# Beaglebone_black.net
KiCad netlist of a schematic drawn in Altium Designer
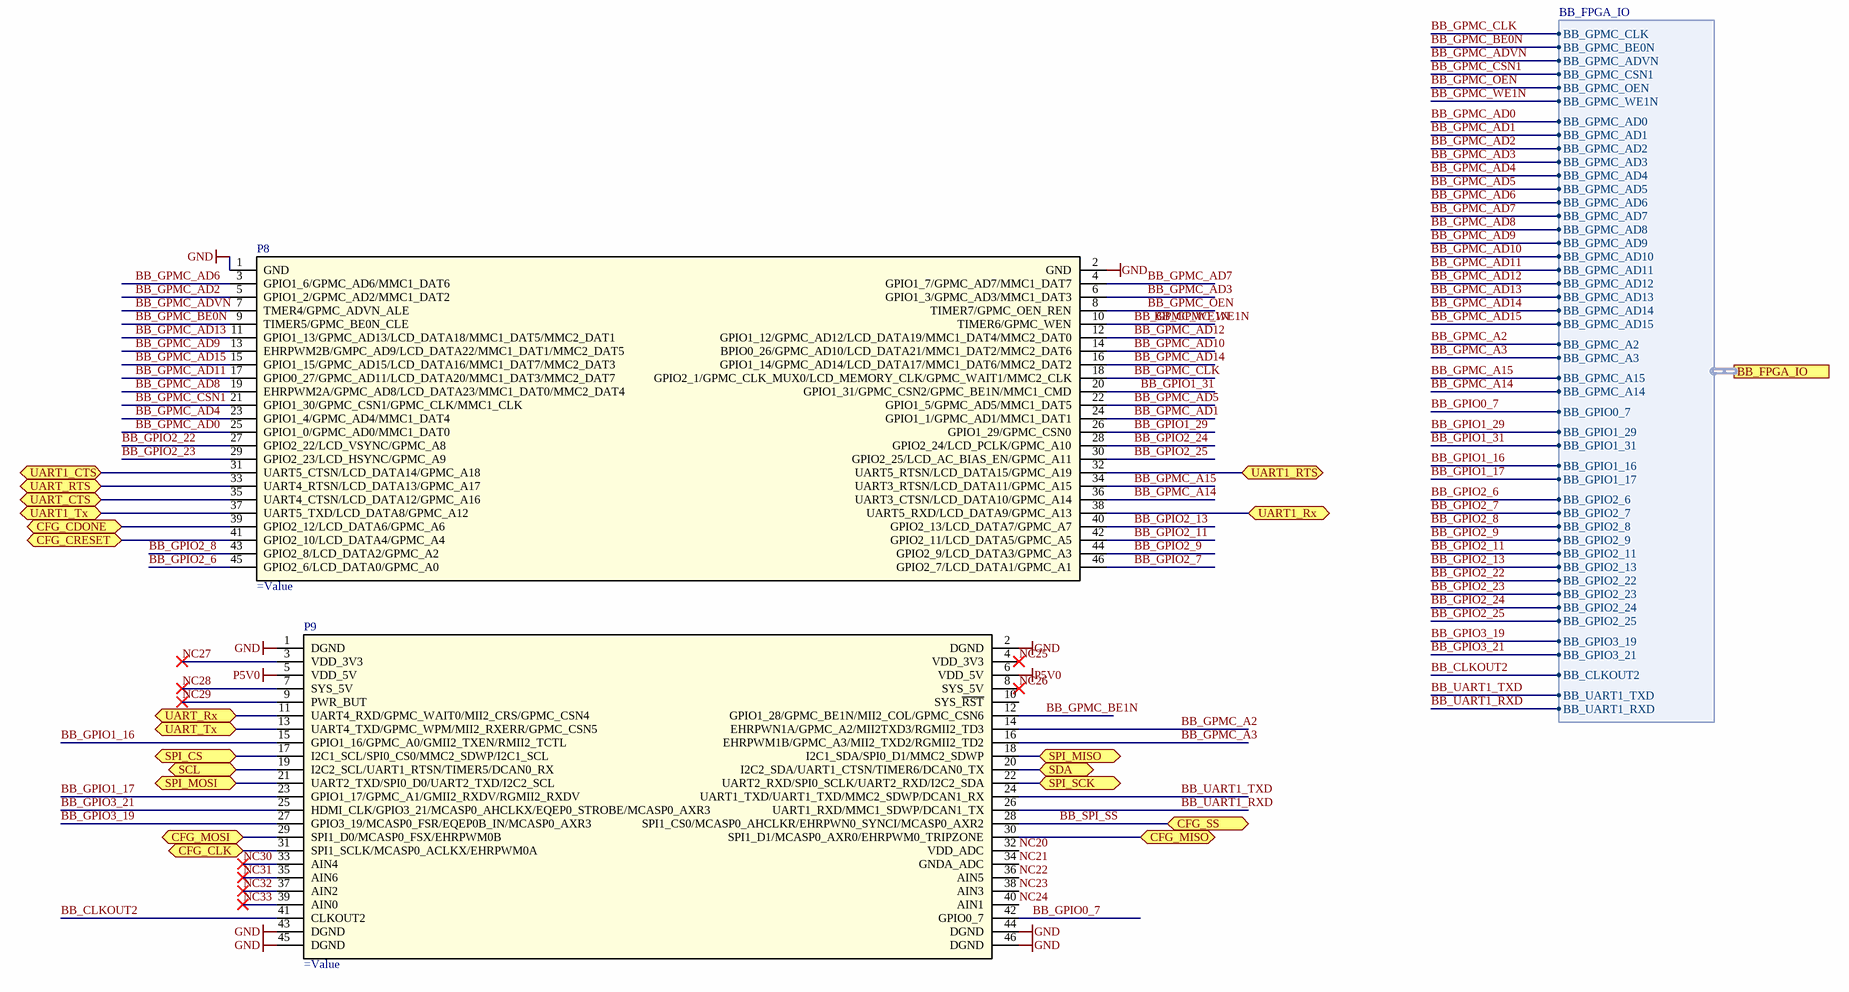
[diagram p0: Beaglebone_black.SchDoc]

(export (version "E")
  (design (tool "Eeschema 10.0.6"))
  (components
    (comp (ref "P8")
      (value "~")
      (footprint "MOD_BEAGLEBONE_P8")
      (description "Beagle_Bone_Black_P8")
      (fields (field (name "MANUFACTURER") "Samtec Inc"))
      (libsource (lib "LIBRARY_SCH") (part "MOD_Beagle_Bone_Black_P8-SSQ"))
    )
    (comp (ref "P9")
      (value "~")
      (footprint "MOD_BEAGLEBONE_P9")
      (description "Beagle_Bone_Black_P9")
      (fields (field (name "MANUFACTURER") "Samtec Inc"))
      (libsource (lib "LIBRARY_SCH") (part "MOD_Beagle_Bone_Black_P9-SSQ"))
    )
  )
  (nets
    (net (code "2") (name "/BB_CLKOUT2") (class "Default")
      (node (ref "P9") (pin "41") (pinfunction "CLKOUT2_41") (pintype "passive"))
    )
    (net (code "3") (name "/BB_GPIO0_7") (class "Default")
      (node (ref "P9") (pin "42") (pinfunction "GPIO0_7_42") (pintype "passive"))
    )
    (net (code "4") (name "/BB_GPIO1_16") (class "Default")
      (node (ref "P9") (pin "15") (pinfunction "GPIO1_16/GPMC_A0/GMII2_TXEN/RMII2_TCTL_15") (pintype "passive"))
    )
    (net (code "5") (name "/BB_GPIO1_17") (class "Default")
      (node (ref "P9") (pin "23") (pinfunction "GPIO1_17/GPMC_A1/GMII2_RXDV/RGMII2_RXDV_23") (pintype "passive"))
    )
    (net (code "6") (name "/BB_GPIO1_29") (class "Default")
      (node (ref "P8") (pin "26") (pinfunction "GPIO1_29/GPMC_CSN0_26") (pintype "passive"))
    )
    (net (code "7") (name "/BB_GPIO1_31") (class "Default")
      (node (ref "P8") (pin "20") (pinfunction "GPIO1_31/GPMC_CSN2/GPMC_BE1N/MMC1_CMD_20") (pintype "passive"))
    )
    (net (code "8") (name "/BB_GPIO2_6") (class "Default")
      (node (ref "P8") (pin "45") (pinfunction "GPIO2_6/LCD_DATA0/GPMC_A0_45") (pintype "passive"))
    )
    (net (code "9") (name "/BB_GPIO2_7") (class "Default")
      (node (ref "P8") (pin "46") (pinfunction "GPIO2_7/LCD_DATA1/GPMC_A1_46") (pintype "passive"))
    )
    (net (code "10") (name "/BB_GPIO2_8") (class "Default")
      (node (ref "P8") (pin "43") (pinfunction "GPIO2_8/LCD_DATA2/GPMC_A2_43") (pintype "passive"))
    )
    (net (code "11") (name "/BB_GPIO2_9") (class "Default")
      (node (ref "P8") (pin "44") (pinfunction "GPIO2_9/LCD_DATA3/GPMC_A3_44") (pintype "passive"))
    )
    (net (code "12") (name "/BB_GPIO2_11") (class "Default")
      (node (ref "P8") (pin "42") (pinfunction "GPIO2_11/LCD_DATA5/GPMC_A5_42") (pintype "passive"))
    )
    (net (code "13") (name "/BB_GPIO2_13") (class "Default")
      (node (ref "P8") (pin "40") (pinfunction "GPIO2_13/LCD_DATA7/GPMC_A7_40") (pintype "passive"))
    )
    (net (code "14") (name "/BB_GPIO2_22") (class "Default")
      (node (ref "P8") (pin "27") (pinfunction "GPIO2_22/LCD_VSYNC/GPMC_A8_27") (pintype "passive"))
    )
    (net (code "15") (name "/BB_GPIO2_23") (class "Default")
      (node (ref "P8") (pin "29") (pinfunction "GPIO2_23/LCD_HSYNC/GPMC_A9_29") (pintype "passive"))
    )
    (net (code "16") (name "/BB_GPIO2_24") (class "Default")
      (node (ref "P8") (pin "28") (pinfunction "GPIO2_24/LCD_PCLK/GPMC_A10_28") (pintype "passive"))
    )
    (net (code "17") (name "/BB_GPIO2_25") (class "Default")
      (node (ref "P8") (pin "30") (pinfunction "GPIO2_25/LCD_AC_BIAS_EN/GPMC_A11_30") (pintype "passive"))
    )
    (net (code "18") (name "/BB_GPIO3_19") (class "Default")
      (node (ref "P9") (pin "27") (pinfunction "GPIO3_19/MCASP0_FSR/EQEP0B_IN/MCASP0_AXR3_27") (pintype "passive"))
    )
    (net (code "19") (name "/BB_GPIO3_21") (class "Default")
      (node (ref "P9") (pin "25") (pinfunction "HDMI_CLK/GPIO3_21/MCASP0_AHCLKX/EQEP0_STROBE/MCASP0_AXR3_25") (pintype "passive"))
    )
    (net (code "20") (name "/BB_GPMC_A2") (class "Default")
      (node (ref "P9") (pin "14") (pinfunction "EHRPWN1A/GPMC_A2/MII2TXD3/RGMII2_TD3_14") (pintype "passive"))
    )
    (net (code "21") (name "/BB_GPMC_A3") (class "Default")
      (node (ref "P9") (pin "16") (pinfunction "EHRPWM1B/GPMC_A3/MII2_TXD2/RGMII2_TD2_16") (pintype "passive"))
    )
    (net (code "22") (name "/BB_GPMC_A14") (class "Default")
      (node (ref "P8") (pin "36") (pinfunction "UART3_CTSN/LCD_DATA10/GPMC_A14_36") (pintype "passive"))
    )
    (net (code "23") (name "/BB_GPMC_A15") (class "Default")
      (node (ref "P8") (pin "34") (pinfunction "UART3_RTSN/LCD_DATA11/GPMC_A15_34") (pintype "passive"))
    )
    (net (code "24") (name "/BB_GPMC_AD0") (class "Default")
      (node (ref "P8") (pin "25") (pinfunction "GPIO1_0/GPMC_AD0/MMC1_DAT0_25") (pintype "passive"))
    )
    (net (code "25") (name "/BB_GPMC_AD1") (class "Default")
      (node (ref "P8") (pin "24") (pinfunction "GPIO1_1/GPMC_AD1/MMC1_DAT1_24") (pintype "passive"))
    )
    (net (code "26") (name "/BB_GPMC_AD2") (class "Default")
      (node (ref "P8") (pin "5") (pinfunction "GPIO1_2/GPMC_AD2/MMC1_DAT2_5") (pintype "passive"))
    )
    (net (code "27") (name "/BB_GPMC_AD3") (class "Default")
      (node (ref "P8") (pin "6") (pinfunction "GPIO1_3/GPMC_AD3/MMC1_DAT3_6") (pintype "passive"))
    )
    (net (code "28") (name "/BB_GPMC_AD4") (class "Default")
      (node (ref "P8") (pin "23") (pinfunction "GPIO1_4/GPMC_AD4/MMC1_DAT4_23") (pintype "passive"))
    )
    (net (code "29") (name "/BB_GPMC_AD5") (class "Default")
      (node (ref "P8") (pin "22") (pinfunction "GPIO1_5/GPMC_AD5/MMC1_DAT5_22") (pintype "passive"))
    )
    (net (code "30") (name "/BB_GPMC_AD6") (class "Default")
      (node (ref "P8") (pin "3") (pinfunction "GPIO1_6/GPMC_AD6/MMC1_DAT6_3") (pintype "passive"))
    )
    (net (code "31") (name "/BB_GPMC_AD7") (class "Default")
      (node (ref "P8") (pin "4") (pinfunction "GPIO1_7/GPMC_AD7/MMC1_DAT7_4") (pintype "passive"))
    )
    (net (code "32") (name "/BB_GPMC_AD8") (class "Default")
      (node (ref "P8") (pin "19") (pinfunction "EHRPWM2A/GPMC_AD8/LCD_DATA23/MMC1_DAT0/MMC2_DAT4_19") (pintype "passive"))
    )
    (net (code "33") (name "/BB_GPMC_AD9") (class "Default")
      (node (ref "P8") (pin "13") (pinfunction "EHRPWM2B/GMPC_AD9/LCD_DATA22/MMC1_DAT1/MMC2_DAT5_13") (pintype "passive"))
    )
    (net (code "34") (name "/BB_GPMC_AD10") (class "Default")
      (node (ref "P8") (pin "14") (pinfunction "BPIO0_26/GPMC_AD10/LCD_DATA21/MMC1_DAT2/MMC2_DAT6_14") (pintype "passive"))
    )
    (net (code "35") (name "/BB_GPMC_AD11") (class "Default")
      (node (ref "P8") (pin "17") (pinfunction "GPIO0_27/GPMC_AD11/LCD_DATA20/MMC1_DAT3/MMC2_DAT7_17") (pintype "passive"))
    )
    (net (code "36") (name "/BB_GPMC_AD12") (class "Default")
      (node (ref "P8") (pin "12") (pinfunction "GPIO1_12/GPMC_AD12/LCD_DATA19/MMC1_DAT4/MMC2_DAT0_12") (pintype "passive"))
    )
    (net (code "37") (name "/BB_GPMC_AD13") (class "Default")
      (node (ref "P8") (pin "11") (pinfunction "GPIO1_13/GPMC_AD13/LCD_DATA18/MMC1_DAT5/MMC2_DAT1_11") (pintype "passive"))
    )
    (net (code "38") (name "/BB_GPMC_AD14") (class "Default")
      (node (ref "P8") (pin "16") (pinfunction "GPIO1_14/GPMC_AD14/LCD_DATA17/MMC1_DAT6/MMC2_DAT2_16") (pintype "passive"))
    )
    (net (code "39") (name "/BB_GPMC_AD15") (class "Default")
      (node (ref "P8") (pin "15") (pinfunction "GPIO1_15/GPMC_AD15/LCD_DATA16/MMC1_DAT7/MMC2_DAT3_15") (pintype "passive"))
    )
    (net (code "40") (name "/BB_GPMC_ADVN") (class "Default")
      (node (ref "P8") (pin "7") (pinfunction "TMER4/GPMC_ADVN_ALE_7") (pintype "passive"))
    )
    (net (code "41") (name "/BB_GPMC_BE0N") (class "Default")
      (node (ref "P8") (pin "9") (pinfunction "TIMER5/GPMC_BE0N_CLE_9") (pintype "passive"))
    )
    (net (code "42") (name "/BB_GPMC_BE1N") (class "Default")
      (node (ref "P9") (pin "12") (pinfunction "GPIO1_28/GPMC_BE1N/MII2_COL/GPMC_CSN6_12") (pintype "passive"))
    )
    (net (code "43") (name "/BB_GPMC_CLK") (class "Default")
      (node (ref "P8") (pin "18") (pinfunction "GPIO2_1/GPMC_CLK_MUX0/LCD_MEMORY_CLK/GPMC_WAIT1/MMC2_CLK_18") (pintype "passive"))
    )
    (net (code "44") (name "/BB_GPMC_CSN1") (class "Default")
      (node (ref "P8") (pin "21") (pinfunction "GPIO1_30/GPMC_CSN1/GPMC_CLK/MMC1_CLK_21") (pintype "passive"))
    )
    (net (code "45") (name "/BB_GPMC_OEN") (class "Default")
      (node (ref "P8") (pin "8") (pinfunction "TIMER7/GPMC_OEN_REN_8") (pintype "passive"))
    )
    (net (code "46") (name "/BB_GPMC_WE1N") (class "Default")
      (node (ref "P8") (pin "10") (pinfunction "TIMER6/GPMC_WEN_10") (pintype "passive"))
    )
    (net (code "47") (name "/BB_SPI_SS") (class "Default")
      (node (ref "P9") (pin "28") (pinfunction "SPI1_CS0/MCASP0_AHCLKR/EHRPWN0_SYNCI/MCASP0_AXR2_28") (pintype "passive"))
    )
    (net (code "48") (name "/BB_UART1_RXD") (class "Default")
      (node (ref "P9") (pin "26") (pinfunction "UART1_RXD/MMC1_SDWP/DCAN1_TX_26") (pintype "passive"))
    )
    (net (code "49") (name "/BB_UART1_TXD") (class "Default")
      (node (ref "P9") (pin "24") (pinfunction "UART1_TXD/UART1_TXD/MMC2_SDWP/DCAN1_RX_24") (pintype "passive"))
    )
    (net (code "50") (name "/CFG_CDONE") (class "Default")
      (node (ref "P8") (pin "39") (pinfunction "GPIO2_12/LCD_DATA6/GPMC_A6_39") (pintype "passive"))
    )
    (net (code "51") (name "/CFG_CLK") (class "Default")
      (node (ref "P9") (pin "31") (pinfunction "SPI1_SCLK/MCASP0_ACLKX/EHRPWM0A_31") (pintype "passive"))
    )
    (net (code "52") (name "/CFG_CRESET") (class "Default")
      (node (ref "P8") (pin "41") (pinfunction "GPIO2_10/LCD_DATA4/GPMC_A4_41") (pintype "passive"))
    )
    (net (code "53") (name "/CFG_MISO") (class "Default")
      (node (ref "P9") (pin "30") (pinfunction "SPI1_D1/MCASP0_AXR0/EHRPWM0_TRIPZONE_30") (pintype "passive"))
    )
    (net (code "54") (name "/CFG_MOSI") (class "Default")
      (node (ref "P9") (pin "29") (pinfunction "SPI1_D0/MCASP0_FSX/EHRPWM0B_29") (pintype "passive"))
    )
    (net (code "55") (name "/NC20") (class "Default")
      (node (ref "P9") (pin "32") (pinfunction "VDD_ADC_32") (pintype "passive"))
    )
    (net (code "56") (name "/NC21") (class "Default")
      (node (ref "P9") (pin "34") (pinfunction "GNDA_ADC_34") (pintype "passive"))
    )
    (net (code "57") (name "/NC22") (class "Default")
      (node (ref "P9") (pin "36") (pinfunction "AIN5_36") (pintype "passive"))
    )
    (net (code "58") (name "/NC23") (class "Default")
      (node (ref "P9") (pin "38") (pinfunction "AIN3_38") (pintype "passive"))
    )
    (net (code "59") (name "/NC24") (class "Default")
      (node (ref "P9") (pin "40") (pinfunction "AIN1_40") (pintype "passive"))
    )
    (net (code "60") (name "/NC25") (class "Default")
      (node (ref "P9") (pin "4") (pinfunction "VDD_3V3_4") (pintype "passive+no_connect"))
    )
    (net (code "61") (name "/NC26") (class "Default")
      (node (ref "P9") (pin "8") (pinfunction "SYS_5V_8") (pintype "passive+no_connect"))
    )
    (net (code "62") (name "/NC27") (class "Default")
      (node (ref "P9") (pin "3") (pinfunction "VDD_3V3_3") (pintype "passive+no_connect"))
    )
    (net (code "63") (name "/NC28") (class "Default")
      (node (ref "P9") (pin "7") (pinfunction "SYS_5V_7") (pintype "passive+no_connect"))
    )
    (net (code "64") (name "/NC29") (class "Default")
      (node (ref "P9") (pin "9") (pinfunction "PWR_BUT_9") (pintype "passive+no_connect"))
    )
    (net (code "65") (name "/NC30") (class "Default")
      (node (ref "P9") (pin "33") (pinfunction "AIN4_33") (pintype "passive+no_connect"))
    )
    (net (code "66") (name "/NC31") (class "Default")
      (node (ref "P9") (pin "35") (pinfunction "AIN6_35") (pintype "passive+no_connect"))
    )
    (net (code "67") (name "/NC32") (class "Default")
      (node (ref "P9") (pin "37") (pinfunction "AIN2_37") (pintype "passive+no_connect"))
    )
    (net (code "68") (name "/NC33") (class "Default")
      (node (ref "P9") (pin "39") (pinfunction "AIN0_39") (pintype "passive+no_connect"))
    )
    (net (code "69") (name "/SCL") (class "Default")
      (node (ref "P9") (pin "19") (pinfunction "I2C2_SCL/UART1_RTSN/TIMER5/DCAN0_RX_19") (pintype "passive"))
    )
    (net (code "70") (name "/SDA") (class "Default")
      (node (ref "P9") (pin "20") (pinfunction "I2C2_SDA/UART1_CTSN/TIMER6/DCAN0_TX_20") (pintype "passive"))
    )
    (net (code "71") (name "/SPI_CS") (class "Default")
      (node (ref "P9") (pin "17") (pinfunction "I2C1_SCL/SPI0_CS0/MMC2_SDWP/I2C1_SCL_17") (pintype "passive"))
    )
    (net (code "72") (name "/SPI_MISO") (class "Default")
      (node (ref "P9") (pin "18") (pinfunction "I2C1_SDA/SPI0_D1/MMC2_SDWP_18") (pintype "passive"))
    )
    (net (code "73") (name "/SPI_MOSI") (class "Default")
      (node (ref "P9") (pin "21") (pinfunction "UART2_TXD/SPI0_D0/UART2_TXD/I2C2_SCL_21") (pintype "passive"))
    )
    (net (code "74") (name "/SPI_SCK") (class "Default")
      (node (ref "P9") (pin "22") (pinfunction "UART2_RXD/SPI0_SCLK/UART2_RXD/I2C2_SDA_22") (pintype "passive"))
    )
    (net (code "75") (name "/UART1_CTS") (class "Default")
      (node (ref "P8") (pin "31") (pinfunction "UART5_CTSN/LCD_DATA14/GPMC_A18_31") (pintype "passive"))
    )
    (net (code "76") (name "/UART1_RTS") (class "Default")
      (node (ref "P8") (pin "32") (pinfunction "UART5_RTSN/LCD_DATA15/GPMC_A19_32") (pintype "passive"))
    )
    (net (code "77") (name "/UART1_Rx") (class "Default")
      (node (ref "P8") (pin "38") (pinfunction "UART5_RXD/LCD_DATA9/GPMC_A13_38") (pintype "passive"))
    )
    (net (code "78") (name "/UART1_Tx") (class "Default")
      (node (ref "P8") (pin "37") (pinfunction "UART5_TXD/LCD_DATA8/GPMC_A12_37") (pintype "passive"))
    )
    (net (code "79") (name "/UART_CTS") (class "Default")
      (node (ref "P8") (pin "35") (pinfunction "UART4_CTSN/LCD_DATA12/GPMC_A16_35") (pintype "passive"))
    )
    (net (code "80") (name "/UART_RTS") (class "Default")
      (node (ref "P8") (pin "33") (pinfunction "UART4_RTSN/LCD_DATA13/GPMC_A17_33") (pintype "passive"))
    )
    (net (code "81") (name "/UART_Rx") (class "Default")
      (node (ref "P9") (pin "11") (pinfunction "UART4_RXD/GPMC_WAIT0/MII2_CRS/GPMC_CSN4_11") (pintype "passive"))
    )
    (net (code "82") (name "/UART_Tx") (class "Default")
      (node (ref "P9") (pin "13") (pinfunction "UART4_TXD/GPMC_WPM/MII2_RXERR/GPMC_CSN5_13") (pintype "passive"))
    )
    (net (code "84") (name "GND") (class "Default")
      (node (ref "P8") (pin "1") (pinfunction "GND_1") (pintype "passive"))
      (node (ref "P8") (pin "2") (pinfunction "GND_2") (pintype "passive"))
      (node (ref "P9") (pin "1") (pinfunction "DGND_1") (pintype "passive"))
      (node (ref "P9") (pin "2") (pinfunction "DGND_2") (pintype "passive"))
      (node (ref "P9") (pin "43") (pinfunction "DGND_43") (pintype "passive"))
      (node (ref "P9") (pin "44") (pinfunction "DGND_44") (pintype "passive"))
      (node (ref "P9") (pin "45") (pinfunction "DGND_45") (pintype "passive"))
      (node (ref "P9") (pin "46") (pinfunction "DGND_46") (pintype "passive"))
    )
    (net (code "85") (name "P5V0") (class "Default")
      (node (ref "P9") (pin "5") (pinfunction "VDD_5V_5") (pintype "passive"))
      (node (ref "P9") (pin "6") (pinfunction "VDD_5V_6") (pintype "passive"))
    )
    (net (code "86") (name "unconnected-(P9-SYS_~{RST}-Pad10)") (class "Default")
      (node (ref "P9") (pin "10") (pinfunction "SYS_~{RST}_10") (pintype "passive"))
    )
  )
)
